# hcpl0630.net
KiCad netlist of a schematic drawn in Altium Designer
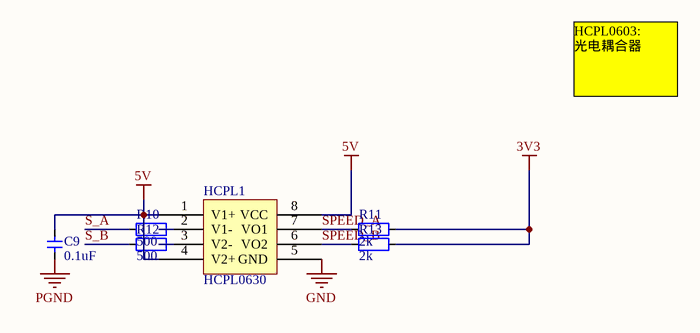
[diagram p0: hcpl0630.SchDoc]

(export (version "E")
  (design (tool "Eeschema 10.0.6"))
  (components
    (comp (ref "C9")
      (value "0.1uF")
      (footprint "CAP_0603")
      (description "Capacitor")
      (fields (field (name "Comment") "Cap_0603"))
      (libsource (lib "Integrated_Library") (part "Cap_0603"))
    )
    (comp (ref "HCPL1")
      (value "HCPL0630")
      (footprint "SOP_E150_8")
      (libsource (lib "K60-mainboard-v3.1") (part "HCPL0630"))
    )
    (comp (ref "R10")
      (value "500")
      (footprint "RES_0603")
      (description "Resistor")
      (fields (field (name "Comment") "Res_0603"))
      (libsource (lib "Integrated_Library") (part "Res_0603"))
    )
    (comp (ref "R11")
      (value "2k")
      (footprint "RES_0603")
      (description "Resistor")
      (fields (field (name "Comment") "Res_0603"))
      (libsource (lib "Integrated_Library") (part "Res_0603"))
    )
    (comp (ref "R12")
      (value "500")
      (footprint "RES_0603")
      (description "Resistor")
      (fields (field (name "Comment") "Res_0603"))
      (libsource (lib "Integrated_Library") (part "Res_0603"))
    )
    (comp (ref "R13")
      (value "2k")
      (footprint "RES_0603")
      (description "Resistor")
      (fields (field (name "Comment") "Res_0603"))
      (libsource (lib "Integrated_Library") (part "Res_0603"))
    )
  )
  (nets
    (net (code "1") (name "/SPEED_A") (class "Default")
      (node (ref "HCPL1") (pin "7") (pinfunction "VO1_7") (pintype "passive"))
      (node (ref "R11") (pin "2") (pinfunction "2_2") (pintype "passive"))
    )
    (net (code "2") (name "/SPEED_B") (class "Default")
      (node (ref "HCPL1") (pin "6") (pinfunction "VO2_6") (pintype "passive"))
      (node (ref "R13") (pin "2") (pinfunction "2_2") (pintype "passive"))
    )
    (net (code "3") (name "/S_A") (class "Default")
      (node (ref "R10") (pin "2") (pinfunction "2_2") (pintype "passive"))
    )
    (net (code "4") (name "/S_B") (class "Default")
      (node (ref "R12") (pin "2") (pinfunction "2_2") (pintype "passive"))
    )
    (net (code "5") (name "3V3") (class "Default")
      (node (ref "R11") (pin "1") (pinfunction "1_1") (pintype "passive"))
      (node (ref "R13") (pin "1") (pinfunction "1_1") (pintype "passive"))
    )
    (net (code "6") (name "5V") (class "Default")
      (node (ref "C9") (pin "2") (pinfunction "2_2") (pintype "passive"))
      (node (ref "HCPL1") (pin "1") (pinfunction "V1+_1") (pintype "passive"))
      (node (ref "HCPL1") (pin "4") (pinfunction "V2+_4") (pintype "passive"))
      (node (ref "HCPL1") (pin "8") (pinfunction "VCC_8") (pintype "passive"))
    )
    (net (code "7") (name "GND") (class "Default")
      (node (ref "HCPL1") (pin "5") (pinfunction "GND_5") (pintype "passive"))
    )
    (net (code "8") (name "Net-(HCPL1-V1-)") (class "Default")
      (node (ref "HCPL1") (pin "2") (pinfunction "V1-_2") (pintype "passive"))
      (node (ref "R10") (pin "1") (pinfunction "1_1") (pintype "passive"))
    )
    (net (code "9") (name "Net-(HCPL1-V2-)") (class "Default")
      (node (ref "HCPL1") (pin "3") (pinfunction "V2-_3") (pintype "passive"))
      (node (ref "R12") (pin "1") (pinfunction "1_1") (pintype "passive"))
    )
    (net (code "10") (name "PGND") (class "Default")
      (node (ref "C9") (pin "1") (pinfunction "1_1") (pintype "passive"))
    )
  )
)
